# 02_Connectors.net
KiCad netlist of a schematic drawn in Altium Designer
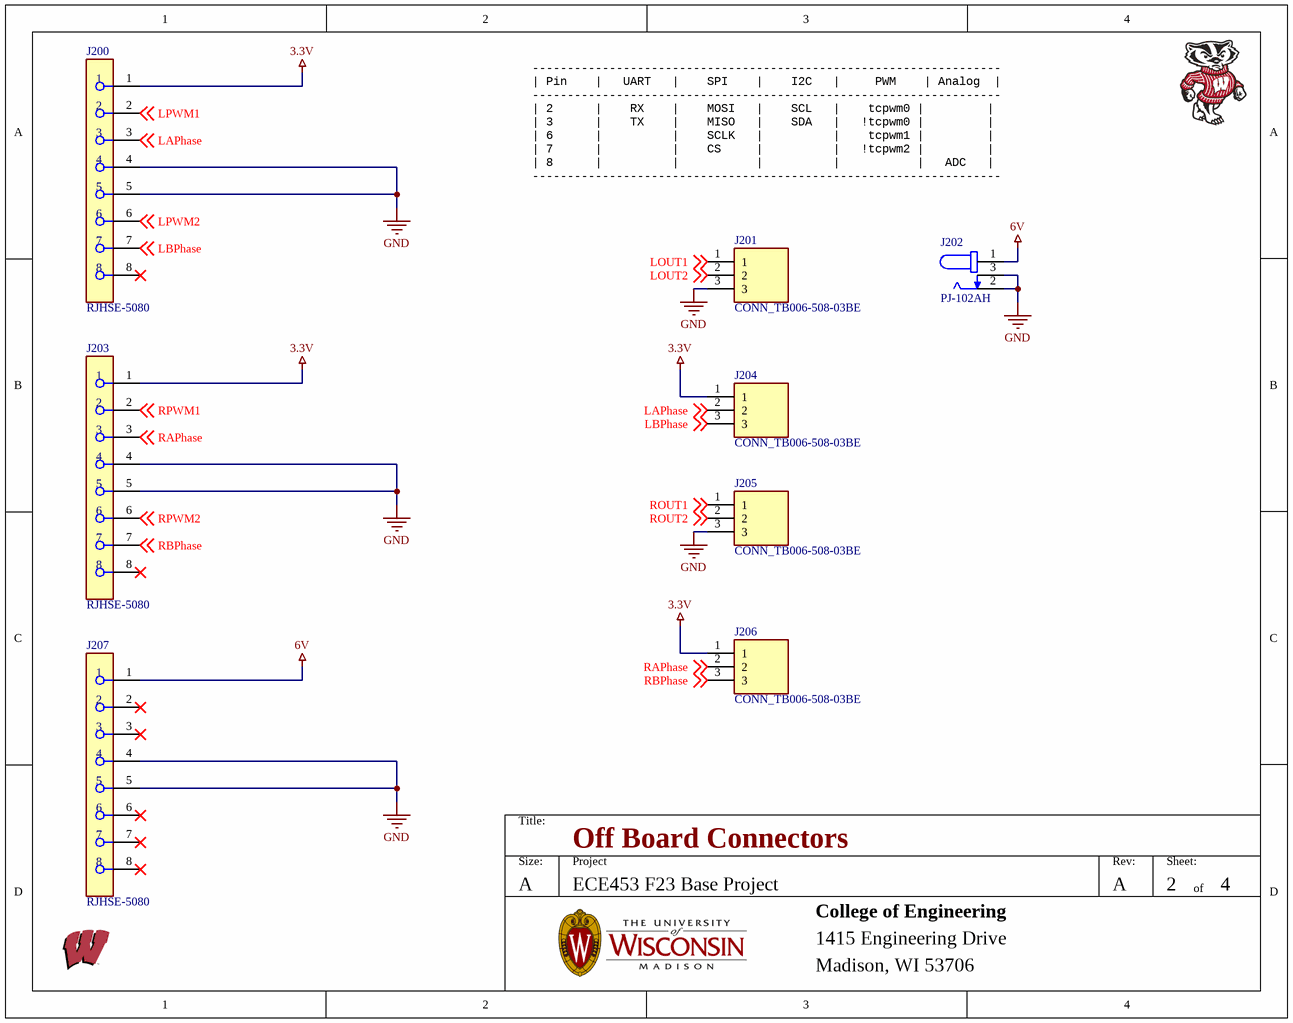
[diagram p0: 02_Connectors.SchDoc]

(export (version "E")
  (design (tool "Eeschema 10.0.6"))
  (components
    (comp (ref "J200")
      (value "RJHSE-5080")
      (footprint "FP-RJHSE-5080-MFG")
      (description "CONN MOD JACK 8P8C R/A UNSHLD")
      (fields
        (field (name "OCTOPART") "https://octopart.com/rjhse-5080-amphenol-45060")
        (field (name "MANUFACTURER") "Amphenol")
      )
      (libsource (lib "Altium Content Vault") (part "b0a0b555dd3abf3683e7c330df25cc4"))
    )
    (comp (ref "J201")
      (value "CONN_TB006-508-03BE")
      (footprint "CUI_TB006-508-03BE")
      (description "2~24 Poles, Screw Type, Horizontal, 5.08 Pitch, 26~14 (AWG), Terminal Block Connector")
      (fields (field (name "MF") "CUI Devices") (field (name "MP") "TB006-508-03BE"))
      (libsource (lib "ECE453_S24") (part "CONN_TB006-508-03BE"))
    )
    (comp (ref "J202")
      (value "PJ-102AH")
      (footprint "CUI_PJ-102AH")
      (description "2.0 x 6.5 mm, 5.0 A, Horizontal, Through Hole, Tapered Pins, Dc Power Jack Connector")
      (fields (field (name "MF") "{'manufacturer': u'CUI Devices'}") (field (name "MANUFACTURER") "CUI"))
      (libsource (lib "ECE453_S24") (part "CONN_PJ-102AH"))
    )
    (comp (ref "J203")
      (value "RJHSE-5080")
      (footprint "FP-RJHSE-5080-MFG")
      (description "CONN MOD JACK 8P8C R/A UNSHLD")
      (fields
        (field (name "OCTOPART") "https://octopart.com/rjhse-5080-amphenol-45060")
        (field (name "MANUFACTURER") "Amphenol")
      )
      (libsource (lib "Altium Content Vault") (part "b0a0b555dd3abf3683e7c330df25cc4"))
    )
    (comp (ref "J204")
      (value "CONN_TB006-508-03BE")
      (footprint "CUI_TB006-508-03BE")
      (description "2~24 Poles, Screw Type, Horizontal, 5.08 Pitch, 26~14 (AWG), Terminal Block Connector")
      (fields (field (name "MF") "CUI Devices") (field (name "MP") "TB006-508-03BE"))
      (libsource (lib "ECE453_S24") (part "CONN_TB006-508-03BE"))
    )
    (comp (ref "J205")
      (value "CONN_TB006-508-03BE")
      (footprint "CUI_TB006-508-03BE")
      (description "2~24 Poles, Screw Type, Horizontal, 5.08 Pitch, 26~14 (AWG), Terminal Block Connector")
      (fields (field (name "MF") "CUI Devices") (field (name "MP") "TB006-508-03BE"))
      (libsource (lib "ECE453_S24") (part "CONN_TB006-508-03BE"))
    )
    (comp (ref "J206")
      (value "CONN_TB006-508-03BE")
      (footprint "CUI_TB006-508-03BE")
      (description "2~24 Poles, Screw Type, Horizontal, 5.08 Pitch, 26~14 (AWG), Terminal Block Connector")
      (fields (field (name "MF") "CUI Devices") (field (name "MP") "TB006-508-03BE"))
      (libsource (lib "ECE453_S24") (part "CONN_TB006-508-03BE"))
    )
    (comp (ref "J207")
      (value "RJHSE-5080")
      (footprint "FP-RJHSE-5080-MFG")
      (description "CONN MOD JACK 8P8C R/A UNSHLD")
      (fields
        (field (name "OCTOPART") "https://octopart.com/rjhse-5080-amphenol-45060")
        (field (name "MANUFACTURER") "Amphenol")
      )
      (libsource (lib "Altium Content Vault") (part "b0a0b555dd3abf3683e7c330df25cc4"))
    )
  )
  (nets
    (net (code "1") (name "3.3V") (class "Default")
      (node (ref "J200") (pin "1") (pinfunction "1_1") (pintype "passive"))
      (node (ref "J203") (pin "1") (pinfunction "1_1") (pintype "passive"))
      (node (ref "J204") (pin "1") (pinfunction "1_1") (pintype "passive"))
      (node (ref "J206") (pin "1") (pinfunction "1_1") (pintype "passive"))
    )
    (net (code "2") (name "6V") (class "Default")
      (node (ref "J202") (pin "1") (pinfunction "1_1") (pintype "passive"))
      (node (ref "J207") (pin "1") (pinfunction "1_1") (pintype "passive"))
    )
    (net (code "3") (name "GND") (class "Default")
      (node (ref "J200") (pin "4") (pinfunction "4_4") (pintype "passive"))
      (node (ref "J200") (pin "5") (pinfunction "5_5") (pintype "passive"))
      (node (ref "J201") (pin "3") (pinfunction "3_3") (pintype "passive"))
      (node (ref "J202") (pin "2") (pinfunction "2_2") (pintype "passive"))
      (node (ref "J202") (pin "3") (pinfunction "3_3") (pintype "passive"))
      (node (ref "J203") (pin "4") (pinfunction "4_4") (pintype "passive"))
      (node (ref "J203") (pin "5") (pinfunction "5_5") (pintype "passive"))
      (node (ref "J205") (pin "3") (pinfunction "3_3") (pintype "passive"))
      (node (ref "J207") (pin "4") (pinfunction "4_4") (pintype "passive"))
      (node (ref "J207") (pin "5") (pinfunction "5_5") (pintype "passive"))
    )
    (net (code "4") (name "LAPhase") (class "Default")
      (node (ref "J200") (pin "3") (pinfunction "3_3") (pintype "passive"))
      (node (ref "J204") (pin "2") (pinfunction "2_2") (pintype "passive"))
    )
    (net (code "5") (name "LBPhase") (class "Default")
      (node (ref "J200") (pin "7") (pinfunction "7_7") (pintype "passive"))
      (node (ref "J204") (pin "3") (pinfunction "3_3") (pintype "passive"))
    )
    (net (code "6") (name "LOUT1") (class "Default")
      (node (ref "J201") (pin "1") (pinfunction "1_1") (pintype "passive"))
    )
    (net (code "7") (name "LOUT2") (class "Default")
      (node (ref "J201") (pin "2") (pinfunction "2_2") (pintype "passive"))
    )
    (net (code "8") (name "LPWM1") (class "Default")
      (node (ref "J200") (pin "2") (pinfunction "2_2") (pintype "passive"))
    )
    (net (code "9") (name "LPWM2") (class "Default")
      (node (ref "J200") (pin "6") (pinfunction "6_6") (pintype "passive"))
    )
    (net (code "10") (name "RAPhase") (class "Default")
      (node (ref "J203") (pin "3") (pinfunction "3_3") (pintype "passive"))
      (node (ref "J206") (pin "2") (pinfunction "2_2") (pintype "passive"))
    )
    (net (code "11") (name "RBPhase") (class "Default")
      (node (ref "J203") (pin "7") (pinfunction "7_7") (pintype "passive"))
      (node (ref "J206") (pin "3") (pinfunction "3_3") (pintype "passive"))
    )
    (net (code "12") (name "ROUT1") (class "Default")
      (node (ref "J205") (pin "1") (pinfunction "1_1") (pintype "passive"))
    )
    (net (code "13") (name "ROUT2") (class "Default")
      (node (ref "J205") (pin "2") (pinfunction "2_2") (pintype "passive"))
    )
    (net (code "14") (name "RPWM1") (class "Default")
      (node (ref "J203") (pin "2") (pinfunction "2_2") (pintype "passive"))
    )
    (net (code "15") (name "RPWM2") (class "Default")
      (node (ref "J203") (pin "6") (pinfunction "6_6") (pintype "passive"))
    )
    (net (code "16") (name "unconnected-(J200-Pad8)") (class "Default")
      (node (ref "J200") (pin "8") (pinfunction "8_8") (pintype "passive+no_connect"))
    )
    (net (code "17") (name "unconnected-(J203-Pad8)") (class "Default")
      (node (ref "J203") (pin "8") (pinfunction "8_8") (pintype "passive+no_connect"))
    )
    (net (code "18") (name "unconnected-(J207-Pad2)") (class "Default")
      (node (ref "J207") (pin "2") (pinfunction "2_2") (pintype "passive+no_connect"))
    )
    (net (code "19") (name "unconnected-(J207-Pad3)") (class "Default")
      (node (ref "J207") (pin "3") (pinfunction "3_3") (pintype "passive+no_connect"))
    )
    (net (code "20") (name "unconnected-(J207-Pad6)") (class "Default")
      (node (ref "J207") (pin "6") (pinfunction "6_6") (pintype "passive+no_connect"))
    )
    (net (code "21") (name "unconnected-(J207-Pad7)") (class "Default")
      (node (ref "J207") (pin "7") (pinfunction "7_7") (pintype "passive+no_connect"))
    )
    (net (code "22") (name "unconnected-(J207-Pad8)") (class "Default")
      (node (ref "J207") (pin "8") (pinfunction "8_8") (pintype "passive+no_connect"))
    )
  )
)
